# Fastino_References.net
KiCad netlist of a schematic drawn in Altium Designer
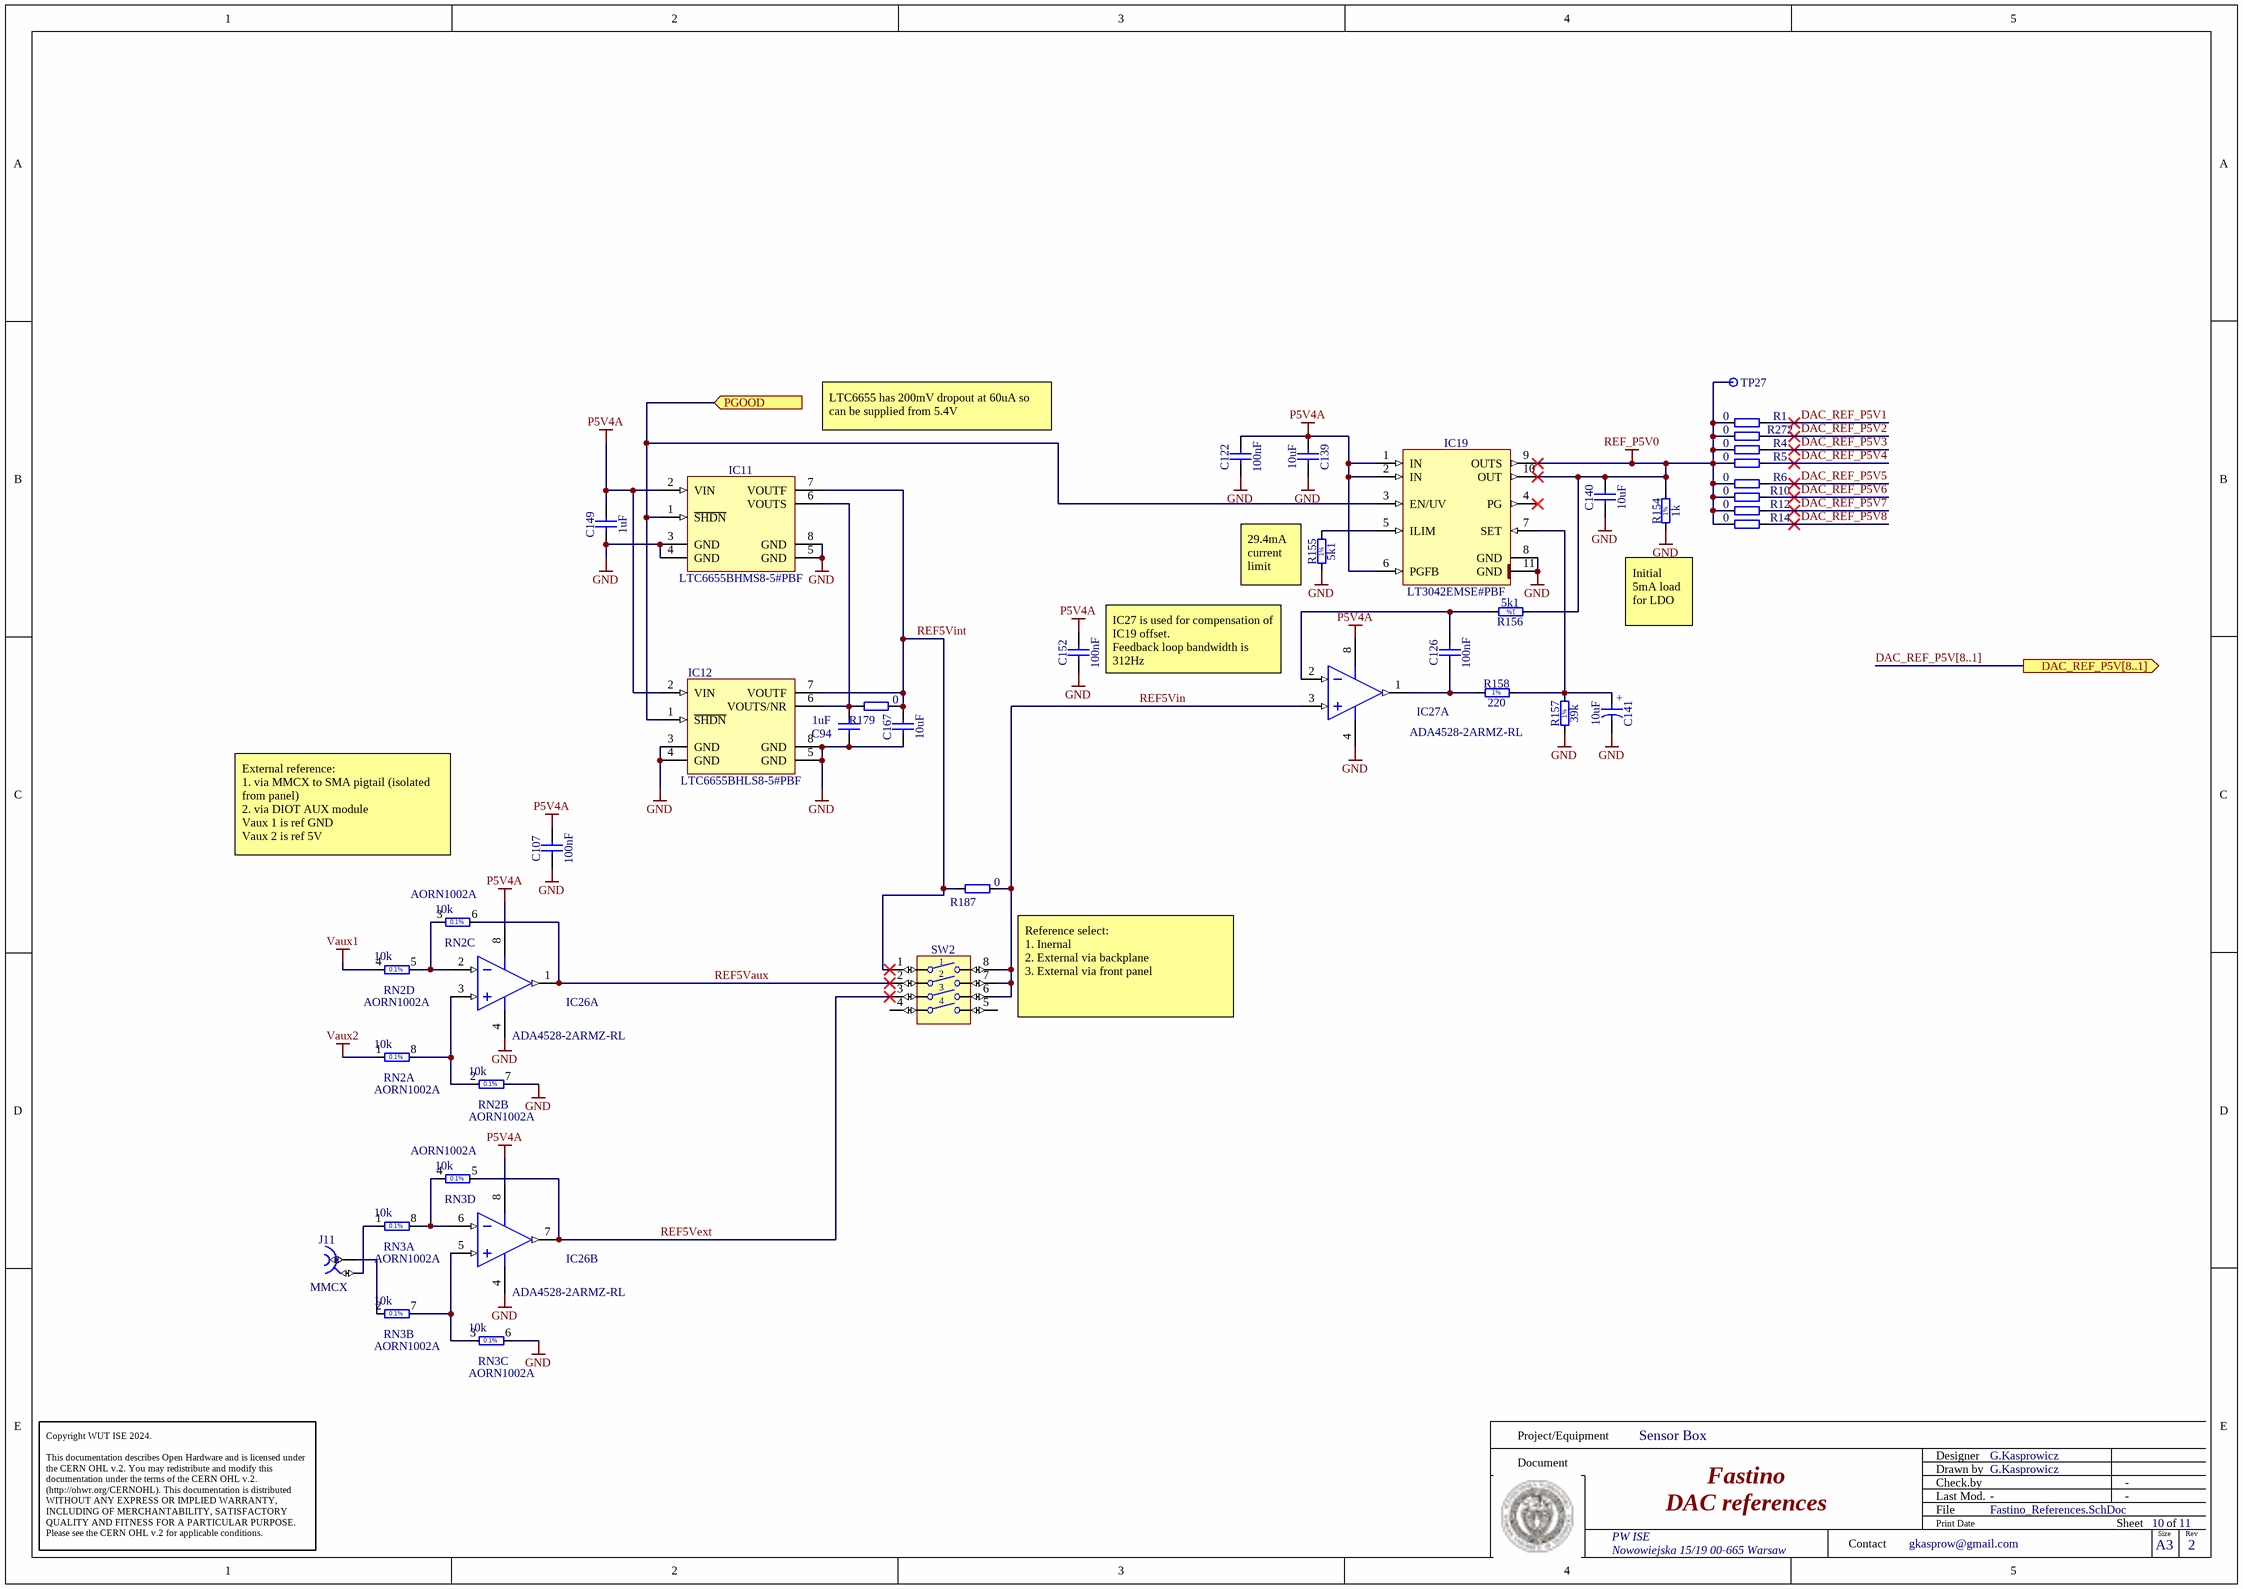
[diagram p0: Fastino_References.SchDoc]

(export (version "E")
  (design (tool "Eeschema 10.0.6"))
  (components
    (comp (ref "C94")
      (value "1uF")
      (footprint "CAPC1608X87N")
      (description "Non-polarised capacitor")
      (fields
        (field (name "PART NUMBER") "CC0603_1UF_25V_10%_X7R")
        (field (name "VOLTAGE") "25V")
        (field (name "AUTHOR") "CERN DEM JLC")
      )
      (libsource (lib "Capacitors") (part "Capacitor - non polarized"))
    )
    (comp (ref "C107")
      (value "100nF")
      (footprint "CAPC1005X55N")
      (description "Non-polarised capacitor")
      (fields
        (field (name "PART NUMBER") "CC0402_100NF_16V_10%_X5R")
        (field (name "VOLTAGE") "16V")
        (field (name "AUTHOR") "CERN DEM JLC")
      )
      (libsource (lib "Capacitors") (part "Capacitor - non polarized"))
    )
    (comp (ref "C122")
      (value "100nF")
      (footprint "CAPC1005X55N")
      (description "Non-polarised capacitor")
      (fields
        (field (name "PART NUMBER") "CC0402_100NF_16V_10%_X5R")
        (field (name "VOLTAGE") "16V")
        (field (name "AUTHOR") "CERN DEM JLC")
      )
      (libsource (lib "Capacitors") (part "Capacitor - non polarized"))
    )
    (comp (ref "C126")
      (value "100nF")
      (footprint "CAPC1005X55N")
      (description "Non-polarised capacitor")
      (fields
        (field (name "PART NUMBER") "CC0402_100NF_16V_10%_X5R")
        (field (name "VOLTAGE") "16V")
        (field (name "AUTHOR") "CERN DEM JLC")
      )
      (libsource (lib "Capacitors") (part "Capacitor - non polarized"))
    )
    (comp (ref "C139")
      (value "10uF")
      (footprint "CAPC1608X80N")
      (description "Non-polarised capacitor")
      (fields
        (field (name "PART NUMBER") "CC0603_10UF_10V_10%_X5R")
        (field (name "VOLTAGE") "10V")
        (field (name "AUTHOR") "CERN DEM JLC")
      )
      (libsource (lib "Capacitors") (part "Capacitor - non polarized"))
    )
    (comp (ref "C140")
      (value "10uF")
      (footprint "CAPC1608X80N")
      (description "Non-polarised capacitor")
      (fields
        (field (name "PART NUMBER") "CC0603_10UF_10V_10%_X5R")
        (field (name "VOLTAGE") "10V")
        (field (name "AUTHOR") "CERN DEM JLC")
      )
      (libsource (lib "Capacitors") (part "Capacitor - non polarized"))
    )
    (comp (ref "C141")
      (value "10uF")
      (footprint "CAPMP3216X180N")
      (description "Polarised capacitor")
      (fields
        (field (name "PART NUMBER") "CTE3216-18_10UF_16V_20%_AVX_TCJ")
        (field (name "VOLTAGE") "16V")
        (field (name "AUTHOR") "CERN DEM JLC")
      )
      (libsource (lib "Capacitors") (part "Capacitor - polarized"))
    )
    (comp (ref "C149")
      (value "1uF")
      (footprint "CAPC1608X87N")
      (description "Non-polarised capacitor")
      (fields
        (field (name "PART NUMBER") "CC0603_1UF_25V_10%_X7R")
        (field (name "VOLTAGE") "25V")
        (field (name "AUTHOR") "CERN DEM JLC")
      )
      (libsource (lib "Capacitors") (part "Capacitor - non polarized"))
    )
    (comp (ref "C152")
      (value "100nF")
      (footprint "CAPC1005X55N")
      (description "Non-polarised capacitor")
      (fields
        (field (name "PART NUMBER") "CC0402_100NF_16V_10%_X5R")
        (field (name "VOLTAGE") "16V")
        (field (name "AUTHOR") "CERN DEM JLC")
      )
      (libsource (lib "Capacitors") (part "Capacitor - non polarized"))
    )
    (comp (ref "C167")
      (value "10uF")
      (footprint "CAPC1608X80N")
      (description "Non-polarised capacitor")
      (fields
        (field (name "PART NUMBER") "CC0603_10UF_10V_10%_X5R")
        (field (name "VOLTAGE") "10V")
        (field (name "AUTHOR") "CERN DEM JLC")
      )
      (libsource (lib "Capacitors") (part "Capacitor - non polarized"))
    )
    (comp (ref "IC11")
      (value "LTC6655BHMS8-5#PBF")
      (footprint "SOP65P490X110-8N")
      (description "0.25ppm Noise, Low Drift Precision Buffered Voltage Reference")
      (fields (field (name "MANUFACTURER") "LINEAR TECHNOLOGY") (field (name "AUTHOR") "CERN DEM JLC"))
      (libsource (lib "ICs And Semiconductors") (part "LTC6655"))
    )
    (comp (ref "IC12")
      (value "LTC6655BHLS8-5#PBF")
      (footprint "8-CLCC")
      (description "5.0V, 1uA Precision Voltage Reference")
      (fields (field (name "MANUFACTURER") "LINEAR TECHNOLOGY") (field (name "AUTHOR") "GK"))
      (libsource (lib "Sampler") (part "REF_LTC6655CHLS8-4.096"))
    )
    (comp (ref "IC19")
      (value "LT3042EMSE#PBF")
      (footprint "SOP50P490X110-11N-R168X198")
      (description "20V, 200mA, Ultralow Noise, Ultrahigh PSRR RF Linear Regulator")
      (fields (field (name "MANUFACTURER") "LINEAR TECHNOLOGY") (field (name "AUTHOR") "CERN DEM MR"))
      (libsource (lib "ICs And Semiconductors") (part "LT3042"))
    )
    (comp (ref "IC26")
      (value "ADA4528-2ARMZ-RL")
      (footprint "ADI-RM-8_N")
      (fields (field (name "GENERIC PART NUMBER") "ADA4528-2") (field (name "MANUFACTURER") "Analog Devices"))
      (libsource (lib "Altium Content Vault") (part "ADI-ADA4000-2-X-8"))
    )
    (comp (ref "IC27")
      (value "ADA4528-2ARMZ-RL")
      (footprint "ADI-RM-8_N")
      (fields (field (name "GENERIC PART NUMBER") "ADA4528-2") (field (name "MANUFACTURER") "Analog Devices"))
      (libsource (lib "Altium Content Vault") (part "ADI-ADA4000-2-X-8"))
    )
    (comp (ref "J11")
      (value "MMCX")
      (footprint "SAMTEC_MMCX-J-P-H-ST-TH1")
      (fields
        (field (name "PART NUMBER") "SAMTEC_MMCX-J-P-H-ST-TH1")
        (field (name "MANUFACTURER") "SAMTEC")
        (field (name "MANUFACTURER PART NUMBER") "MMCX-J-P-H-ST-TH1")
        (field (name "AUTHOR") "CERN DEM JLC")
      )
      (libsource (lib "Connectors") (part "Coax_1Female_1Shield"))
    )
    (comp (ref "R1")
      (value "0")
      (footprint "RESC1005X40N")
      (description "Resistor")
      (fields
        (field (name "PART NUMBER") "R0402_0R_JUMPER")
        (field (name "MANUFACTURER") "GENERIC")
        (field (name "AUTHOR") "CERN DEM JLC")
      )
      (libsource (lib "Resistors") (part "Resistor"))
    )
    (comp (ref "R4")
      (value "0")
      (footprint "RESC1005X40N")
      (description "Resistor")
      (fields
        (field (name "PART NUMBER") "R0402_0R_JUMPER")
        (field (name "MANUFACTURER") "GENERIC")
        (field (name "AUTHOR") "CERN DEM JLC")
      )
      (libsource (lib "Resistors") (part "Resistor"))
    )
    (comp (ref "R5")
      (value "0")
      (footprint "RESC1005X40N")
      (description "Resistor")
      (fields
        (field (name "PART NUMBER") "R0402_0R_JUMPER")
        (field (name "MANUFACTURER") "GENERIC")
        (field (name "AUTHOR") "CERN DEM JLC")
      )
      (libsource (lib "Resistors") (part "Resistor"))
    )
    (comp (ref "R6")
      (value "0")
      (footprint "RESC1005X40N")
      (description "Resistor")
      (fields
        (field (name "PART NUMBER") "R0402_0R_JUMPER")
        (field (name "MANUFACTURER") "GENERIC")
        (field (name "AUTHOR") "CERN DEM JLC")
      )
      (libsource (lib "Resistors") (part "Resistor"))
    )
    (comp (ref "R10")
      (value "0")
      (footprint "RESC1005X40N")
      (description "Resistor")
      (fields
        (field (name "PART NUMBER") "R0402_0R_JUMPER")
        (field (name "MANUFACTURER") "GENERIC")
        (field (name "AUTHOR") "CERN DEM JLC")
      )
      (libsource (lib "Resistors") (part "Resistor"))
    )
    (comp (ref "R12")
      (value "0")
      (footprint "RESC1005X40N")
      (description "Resistor")
      (fields
        (field (name "PART NUMBER") "R0402_0R_JUMPER")
        (field (name "MANUFACTURER") "GENERIC")
        (field (name "AUTHOR") "CERN DEM JLC")
      )
      (libsource (lib "Resistors") (part "Resistor"))
    )
    (comp (ref "R14")
      (value "0")
      (footprint "RESC1005X40N")
      (description "Resistor")
      (fields
        (field (name "PART NUMBER") "R0402_0R_JUMPER")
        (field (name "MANUFACTURER") "GENERIC")
        (field (name "AUTHOR") "CERN DEM JLC")
      )
      (libsource (lib "Resistors") (part "Resistor"))
    )
    (comp (ref "R154")
      (value "1k")
      (footprint "RESC1005X40N")
      (description "Resistor - 1%")
      (fields
        (field (name "PART NUMBER") "R0402_1K_1%_0.0625W_100PPM")
        (field (name "POWER") "0.0625W")
        (field (name "AUTHOR") "CERN DEM JLC")
      )
      (libsource (lib "Resistors") (part "Resistor - 1%"))
    )
    (comp (ref "R155")
      (value "5k1")
      (footprint "RESC1005X40N")
      (description "Resistor - 1%")
      (fields
        (field (name "PART NUMBER") "R0402_5K1_1%_0.0625W_100PPM")
        (field (name "POWER") "0.0625W")
        (field (name "AUTHOR") "CERN DEM JLC")
      )
      (libsource (lib "Resistors") (part "Resistor - 1%"))
    )
    (comp (ref "R156")
      (value "5k1")
      (footprint "RESC1005X40N")
      (description "Resistor - 1%")
      (fields
        (field (name "PART NUMBER") "R0402_5K1_1%_0.0625W_100PPM")
        (field (name "POWER") "0.0625W")
        (field (name "AUTHOR") "CERN DEM JLC")
      )
      (libsource (lib "Resistors") (part "Resistor - 1%"))
    )
    (comp (ref "R157")
      (value "39k")
      (footprint "RESC1608X55N")
      (description "Resistor - 1%")
      (fields
        (field (name "PART NUMBER") "R0603_39K_1%_0.1W_100PPM")
        (field (name "POWER") "0.1W")
        (field (name "AUTHOR") "CERN DEM JLC")
      )
      (libsource (lib "Resistors") (part "Resistor - 1%"))
    )
    (comp (ref "R158")
      (value "220")
      (footprint "RESC1005X40N")
      (description "Resistor - 1%")
      (fields
        (field (name "PART NUMBER") "R0402_220R_1%_0.0625W_100PPM")
        (field (name "POWER") "0.0625W")
        (field (name "AUTHOR") "CERN DEM JLC")
      )
      (libsource (lib "Resistors") (part "Resistor - 1%"))
    )
    (comp (ref "R179")
      (value "0")
      (footprint "RESC1005X40N")
      (description "Resistor")
      (fields
        (field (name "PART NUMBER") "R0402_0R_JUMPER")
        (field (name "MANUFACTURER") "GENERIC")
        (field (name "AUTHOR") "CERN DEM JLC")
      )
      (libsource (lib "Resistors") (part "Resistor"))
    )
    (comp (ref "R187")
      (value "0")
      (footprint "RESC1005X40N")
      (description "Resistor")
      (fields
        (field (name "PART NUMBER") "R0402_0R_JUMPER")
        (field (name "MANUFACTURER") "GENERIC")
        (field (name "AUTHOR") "CERN DEM JLC")
      )
      (libsource (lib "Resistors") (part "Resistor"))
    )
    (comp (ref "R272")
      (value "0")
      (footprint "RESC1005X40N")
      (description "Resistor")
      (fields
        (field (name "PART NUMBER") "R0402_0R_JUMPER")
        (field (name "MANUFACTURER") "GENERIC")
        (field (name "AUTHOR") "CERN DEM JLC")
      )
      (libsource (lib "Resistors") (part "Resistor"))
    )
    (comp (ref "RN2")
      (value "10k")
      (footprint "SOIC127P600X175-8N")
      (description "DIL8 Resistor Network 4 Isolated Resistor 0.1%")
      (fields
        (field (name "PART NUMBER") "RN_10K_VISHAY_AORN1002A")
        (field (name "POWER") "4x0.1W")
        (field (name "MANUFACTURER PART NUMBER") "AORN1002A")
        (field (name "AUTHOR") "CERN DEM JLC")
      )
      (libsource (lib "Resistors") (part "RN DIL8_4xR_Isolated_0.1%"))
    )
    (comp (ref "RN3")
      (value "10k")
      (footprint "SOIC127P600X175-8N")
      (description "DIL8 Resistor Network 4 Isolated Resistor 0.1%")
      (fields
        (field (name "PART NUMBER") "RN_10K_VISHAY_AORN1002A")
        (field (name "POWER") "4x0.1W")
        (field (name "MANUFACTURER PART NUMBER") "AORN1002A")
        (field (name "AUTHOR") "CERN DEM JLC")
      )
      (libsource (lib "Resistors") (part "RN DIL8_4xR_Isolated_0.1%"))
    )
    (comp (ref "SW2")
      (value "Switch")
      (footprint "SW_TYCO_1571983-4")
      (description "4 Ways SPST DIP Switch")
      (fields
        (field (name "PART NUMBER") "SW_TYCO_1571983-4")
        (field (name "MANUFACTURER") "TYCO")
        (field (name "AUTHOR") "CERN DEM JLC")
      )
      (libsource (lib "Eletro-mechanical") (part "SW 4x SPST DIP Switch"))
    )
    (comp (ref "TP27")
      (value "Test Point")
      (footprint "TPS127")
      (fields (field (name "PART NUMBER") "SMD_PAD_1.27X1.27MM") (field (name "AUTHOR") "CERN DEM JLC"))
      (libsource (lib "Eletro-mechanical") (part "Test Point"))
    )
  )
  (nets
    (net (code "1") (name "/DAC_REF_P5V1") (class "Default")
      (node (ref "R1") (pin "2") (pinfunction "2_2") (pintype "passive"))
    )
    (net (code "2") (name "/DAC_REF_P5V2") (class "Default")
      (node (ref "R272") (pin "2") (pinfunction "2_2") (pintype "passive"))
    )
    (net (code "3") (name "/DAC_REF_P5V3") (class "Default")
      (node (ref "R4") (pin "2") (pinfunction "2_2") (pintype "passive"))
    )
    (net (code "4") (name "/DAC_REF_P5V4") (class "Default")
      (node (ref "R5") (pin "2") (pinfunction "2_2") (pintype "passive"))
    )
    (net (code "5") (name "/DAC_REF_P5V5") (class "Default")
      (node (ref "R6") (pin "2") (pinfunction "2_2") (pintype "passive"))
    )
    (net (code "6") (name "/DAC_REF_P5V6") (class "Default")
      (node (ref "R10") (pin "2") (pinfunction "2_2") (pintype "passive"))
    )
    (net (code "7") (name "/DAC_REF_P5V7") (class "Default")
      (node (ref "R12") (pin "2") (pinfunction "2_2") (pintype "passive"))
    )
    (net (code "8") (name "/DAC_REF_P5V8") (class "Default")
      (node (ref "R14") (pin "2") (pinfunction "2_2") (pintype "passive"))
    )
    (net (code "10") (name "/PGOOD") (class "Default")
      (node (ref "IC11") (pin "1") (pinfunction "~{SHDN}_1") (pintype "input"))
      (node (ref "IC12") (pin "1") (pinfunction "~{SHDN}_1") (pintype "input"))
      (node (ref "IC19") (pin "3") (pinfunction "EN/UV_3") (pintype "input"))
    )
    (net (code "11") (name "/REF5Vaux") (class "Default")
      (node (ref "IC26") (pin "1") (pinfunction "OUT_A_1") (pintype "output"))
      (node (ref "RN2") (pin "6") (pinfunction "6_6") (pintype "passive"))
      (node (ref "SW2") (pin "2") (pinfunction "2_2") (pintype "bidirectional"))
    )
    (net (code "12") (name "/REF5Vext") (class "Default")
      (node (ref "IC26") (pin "7") (pinfunction "OUT_B_7") (pintype "output"))
      (node (ref "RN3") (pin "5") (pinfunction "5_5") (pintype "passive"))
      (node (ref "SW2") (pin "3") (pinfunction "3_3") (pintype "bidirectional"))
    )
    (net (code "13") (name "/REF5Vin") (class "Default")
      (node (ref "IC27") (pin "3") (pinfunction "+IN_A_3") (pintype "input"))
      (node (ref "R187") (pin "2") (pinfunction "2_2") (pintype "passive"))
      (node (ref "SW2") (pin "6") (pinfunction "6_6") (pintype "bidirectional"))
      (node (ref "SW2") (pin "7") (pinfunction "7_7") (pintype "bidirectional"))
      (node (ref "SW2") (pin "8") (pinfunction "8_8") (pintype "bidirectional"))
    )
    (net (code "14") (name "/REF5Vint") (class "Default")
      (node (ref "C167") (pin "2") (pinfunction "2_2") (pintype "passive"))
      (node (ref "IC11") (pin "7") (pinfunction "VOUTF_7") (pintype "power_in"))
      (node (ref "IC12") (pin "7") (pinfunction "VOUTF_7") (pintype "power_in"))
      (node (ref "R179") (pin "2") (pinfunction "2_2") (pintype "passive"))
      (node (ref "R187") (pin "1") (pinfunction "1_1") (pintype "passive"))
      (node (ref "SW2") (pin "1") (pinfunction "1_1") (pintype "bidirectional"))
    )
    (net (code "15") (name "GND") (class "Default")
      (node (ref "C107") (pin "1") (pinfunction "1_1") (pintype "passive"))
      (node (ref "C122") (pin "1") (pinfunction "1_1") (pintype "passive"))
      (node (ref "C139") (pin "2") (pinfunction "2_2") (pintype "passive"))
      (node (ref "C140") (pin "1") (pinfunction "1_1") (pintype "passive"))
      (node (ref "C141") (pin "2") (pinfunction "2_2") (pintype "passive"))
      (node (ref "C149") (pin "1") (pinfunction "1_1") (pintype "passive"))
      (node (ref "C152") (pin "1") (pinfunction "1_1") (pintype "passive"))
      (node (ref "C167") (pin "1") (pinfunction "1_1") (pintype "passive"))
      (node (ref "C94") (pin "1") (pinfunction "1_1") (pintype "passive"))
      (node (ref "IC11") (pin "3") (pinfunction "GND_3") (pintype "power_in"))
      (node (ref "IC11") (pin "4") (pinfunction "GND_4") (pintype "power_in"))
      (node (ref "IC11") (pin "5") (pinfunction "GND_5") (pintype "power_in"))
      (node (ref "IC11") (pin "8") (pinfunction "GND_8") (pintype "power_in"))
      (node (ref "IC12") (pin "3") (pinfunction "GND_3") (pintype "power_in"))
      (node (ref "IC12") (pin "4") (pinfunction "GND_4") (pintype "power_in"))
      (node (ref "IC12") (pin "5") (pinfunction "GND_5") (pintype "power_in"))
      (node (ref "IC12") (pin "8") (pinfunction "GND_8") (pintype "power_in"))
      (node (ref "IC19") (pin "11") (pinfunction "GND_11") (pintype "power_in"))
      (node (ref "IC19") (pin "8") (pinfunction "GND_8") (pintype "power_in"))
      (node (ref "IC26") (pin "4") (pinfunction "-V_4") (pintype "power_in"))
      (node (ref "IC27") (pin "4") (pinfunction "-V_4") (pintype "power_in"))
      (node (ref "R154") (pin "1") (pinfunction "1_1") (pintype "passive"))
      (node (ref "R155") (pin "1") (pinfunction "1_1") (pintype "passive"))
      (node (ref "R157") (pin "1") (pinfunction "1_1") (pintype "passive"))
      (node (ref "RN2") (pin "7") (pinfunction "7_7") (pintype "passive"))
      (node (ref "RN3") (pin "6") (pinfunction "6_6") (pintype "passive"))
    )
    (net (code "16") (name "Net-(IC11-VOUTS)") (class "Default")
      (node (ref "C94") (pin "2") (pinfunction "2_2") (pintype "passive"))
      (node (ref "IC11") (pin "6") (pinfunction "VOUTS_6") (pintype "power_in"))
      (node (ref "IC12") (pin "6") (pinfunction "VOUTS/NR_6") (pintype "power_in"))
      (node (ref "R179") (pin "1") (pinfunction "1_1") (pintype "passive"))
    )
    (net (code "17") (name "Net-(IC19-ILIM)") (class "Default")
      (node (ref "IC19") (pin "5") (pinfunction "ILIM_5") (pintype "input"))
      (node (ref "R155") (pin "2") (pinfunction "2_2") (pintype "passive"))
    )
    (net (code "18") (name "Net-(IC19-SET)") (class "Default")
      (node (ref "C141") (pin "1") (pinfunction "1_1") (pintype "passive"))
      (node (ref "IC19") (pin "7") (pinfunction "SET_7") (pintype "input"))
      (node (ref "R157") (pin "2") (pinfunction "2_2") (pintype "passive"))
      (node (ref "R158") (pin "2") (pinfunction "2_2") (pintype "passive"))
    )
    (net (code "19") (name "Net-(IC26A-+IN_A)") (class "Default")
      (node (ref "IC26") (pin "3") (pinfunction "+IN_A_3") (pintype "input"))
      (node (ref "RN2") (pin "2") (pinfunction "2_2") (pintype "passive"))
      (node (ref "RN2") (pin "8") (pinfunction "8_8") (pintype "passive"))
    )
    (net (code "20") (name "Net-(IC26A--IN_A)") (class "Default")
      (node (ref "IC26") (pin "2") (pinfunction "-IN_A_2") (pintype "input"))
      (node (ref "RN2") (pin "3") (pinfunction "3_3") (pintype "passive"))
      (node (ref "RN2") (pin "5") (pinfunction "5_5") (pintype "passive"))
    )
    (net (code "21") (name "Net-(IC26B-+IN_B)") (class "Default")
      (node (ref "IC26") (pin "5") (pinfunction "+IN_B_5") (pintype "input"))
      (node (ref "RN3") (pin "3") (pinfunction "3_3") (pintype "passive"))
      (node (ref "RN3") (pin "7") (pinfunction "7_7") (pintype "passive"))
    )
    (net (code "22") (name "Net-(IC26B--IN_B)") (class "Default")
      (node (ref "IC26") (pin "6") (pinfunction "-IN_B_6") (pintype "input"))
      (node (ref "RN3") (pin "4") (pinfunction "4_4") (pintype "passive"))
      (node (ref "RN3") (pin "8") (pinfunction "8_8") (pintype "passive"))
    )
    (net (code "23") (name "Net-(IC27A--IN_A)") (class "Default")
      (node (ref "C126") (pin "2") (pinfunction "2_2") (pintype "passive"))
      (node (ref "IC27") (pin "2") (pinfunction "-IN_A_2") (pintype "input"))
      (node (ref "R156") (pin "2") (pinfunction "2_2") (pintype "passive"))
    )
    (net (code "24") (name "Net-(IC27A-OUT_A)") (class "Default")
      (node (ref "C126") (pin "1") (pinfunction "1_1") (pintype "passive"))
      (node (ref "IC27") (pin "1") (pinfunction "OUT_A_1") (pintype "output"))
      (node (ref "R158") (pin "1") (pinfunction "1_1") (pintype "passive"))
    )
    (net (code "25") (name "Net-(J11-Pad1)") (class "Default")
      (node (ref "J11") (pin "1") (pinfunction "1_1") (pintype "bidirectional"))
      (node (ref "RN3") (pin "2") (pinfunction "2_2") (pintype "passive"))
    )
    (net (code "26") (name "Net-(J11-Pad2)") (class "Default")
      (node (ref "J11") (pin "2") (pinfunction "2_2") (pintype "bidirectional"))
      (node (ref "RN3") (pin "1") (pinfunction "1_1") (pintype "passive"))
    )
    (net (code "27") (name "P5V4A") (class "Default")
      (node (ref "C107") (pin "2") (pinfunction "2_2") (pintype "passive"))
      (node (ref "C122") (pin "2") (pinfunction "2_2") (pintype "passive"))
      (node (ref "C139") (pin "1") (pinfunction "1_1") (pintype "passive"))
      (node (ref "C149") (pin "2") (pinfunction "2_2") (pintype "passive"))
      (node (ref "C152") (pin "2") (pinfunction "2_2") (pintype "passive"))
      (node (ref "IC11") (pin "2") (pinfunction "VIN_2") (pintype "input"))
      (node (ref "IC12") (pin "2") (pinfunction "VIN_2") (pintype "input"))
      (node (ref "IC19") (pin "1") (pinfunction "IN_1") (pintype "input"))
      (node (ref "IC19") (pin "2") (pinfunction "IN_2") (pintype "input"))
      (node (ref "IC19") (pin "6") (pinfunction "PGFB_6") (pintype "input"))
      (node (ref "IC26") (pin "8") (pinfunction "+V_8") (pintype "power_in"))
      (node (ref "IC27") (pin "8") (pinfunction "+V_8") (pintype "power_in"))
    )
    (net (code "28") (name "REF_P5V0") (class "Default")
      (node (ref "C140") (pin "2") (pinfunction "2_2") (pintype "passive"))
      (node (ref "IC19") (pin "10") (pinfunction "OUT_10") (pintype "output"))
      (node (ref "IC19") (pin "9") (pinfunction "OUTS_9") (pintype "output"))
      (node (ref "R1") (pin "1") (pinfunction "1_1") (pintype "passive"))
      (node (ref "R10") (pin "1") (pinfunction "1_1") (pintype "passive"))
      (node (ref "R12") (pin "1") (pinfunction "1_1") (pintype "passive"))
      (node (ref "R14") (pin "1") (pinfunction "1_1") (pintype "passive"))
      (node (ref "R154") (pin "2") (pinfunction "2_2") (pintype "passive"))
      (node (ref "R156") (pin "1") (pinfunction "1_1") (pintype "passive"))
      (node (ref "R272") (pin "1") (pinfunction "1_1") (pintype "passive"))
      (node (ref "R4") (pin "1") (pinfunction "1_1") (pintype "passive"))
      (node (ref "R5") (pin "1") (pinfunction "1_1") (pintype "passive"))
      (node (ref "R6") (pin "1") (pinfunction "1_1") (pintype "passive"))
      (node (ref "TP27") (pin "1") (pinfunction "1_1") (pintype "bidirectional"))
    )
    (net (code "29") (name "Vaux1") (class "Default")
      (node (ref "RN2") (pin "4") (pinfunction "4_4") (pintype "passive"))
    )
    (net (code "30") (name "Vaux2") (class "Default")
      (node (ref "RN2") (pin "1") (pinfunction "1_1") (pintype "passive"))
    )
    (net (code "31") (name "unconnected-(IC19-PG-Pad4)") (class "Default")
      (node (ref "IC19") (pin "4") (pinfunction "PG_4") (pintype "output+no_connect"))
    )
    (net (code "32") (name "unconnected-(SW2-Pad4)") (class "Default")
      (node (ref "SW2") (pin "4") (pinfunction "4_4") (pintype "bidirectional"))
    )
    (net (code "33") (name "unconnected-(SW2-Pad5)") (class "Default")
      (node (ref "SW2") (pin "5") (pinfunction "5_5") (pintype "bidirectional"))
    )
  )
)
